# Pendeteksi_Kebusukan_Berbasis_IOT.net
KiCad netlist of a schematic drawn in EAGLE
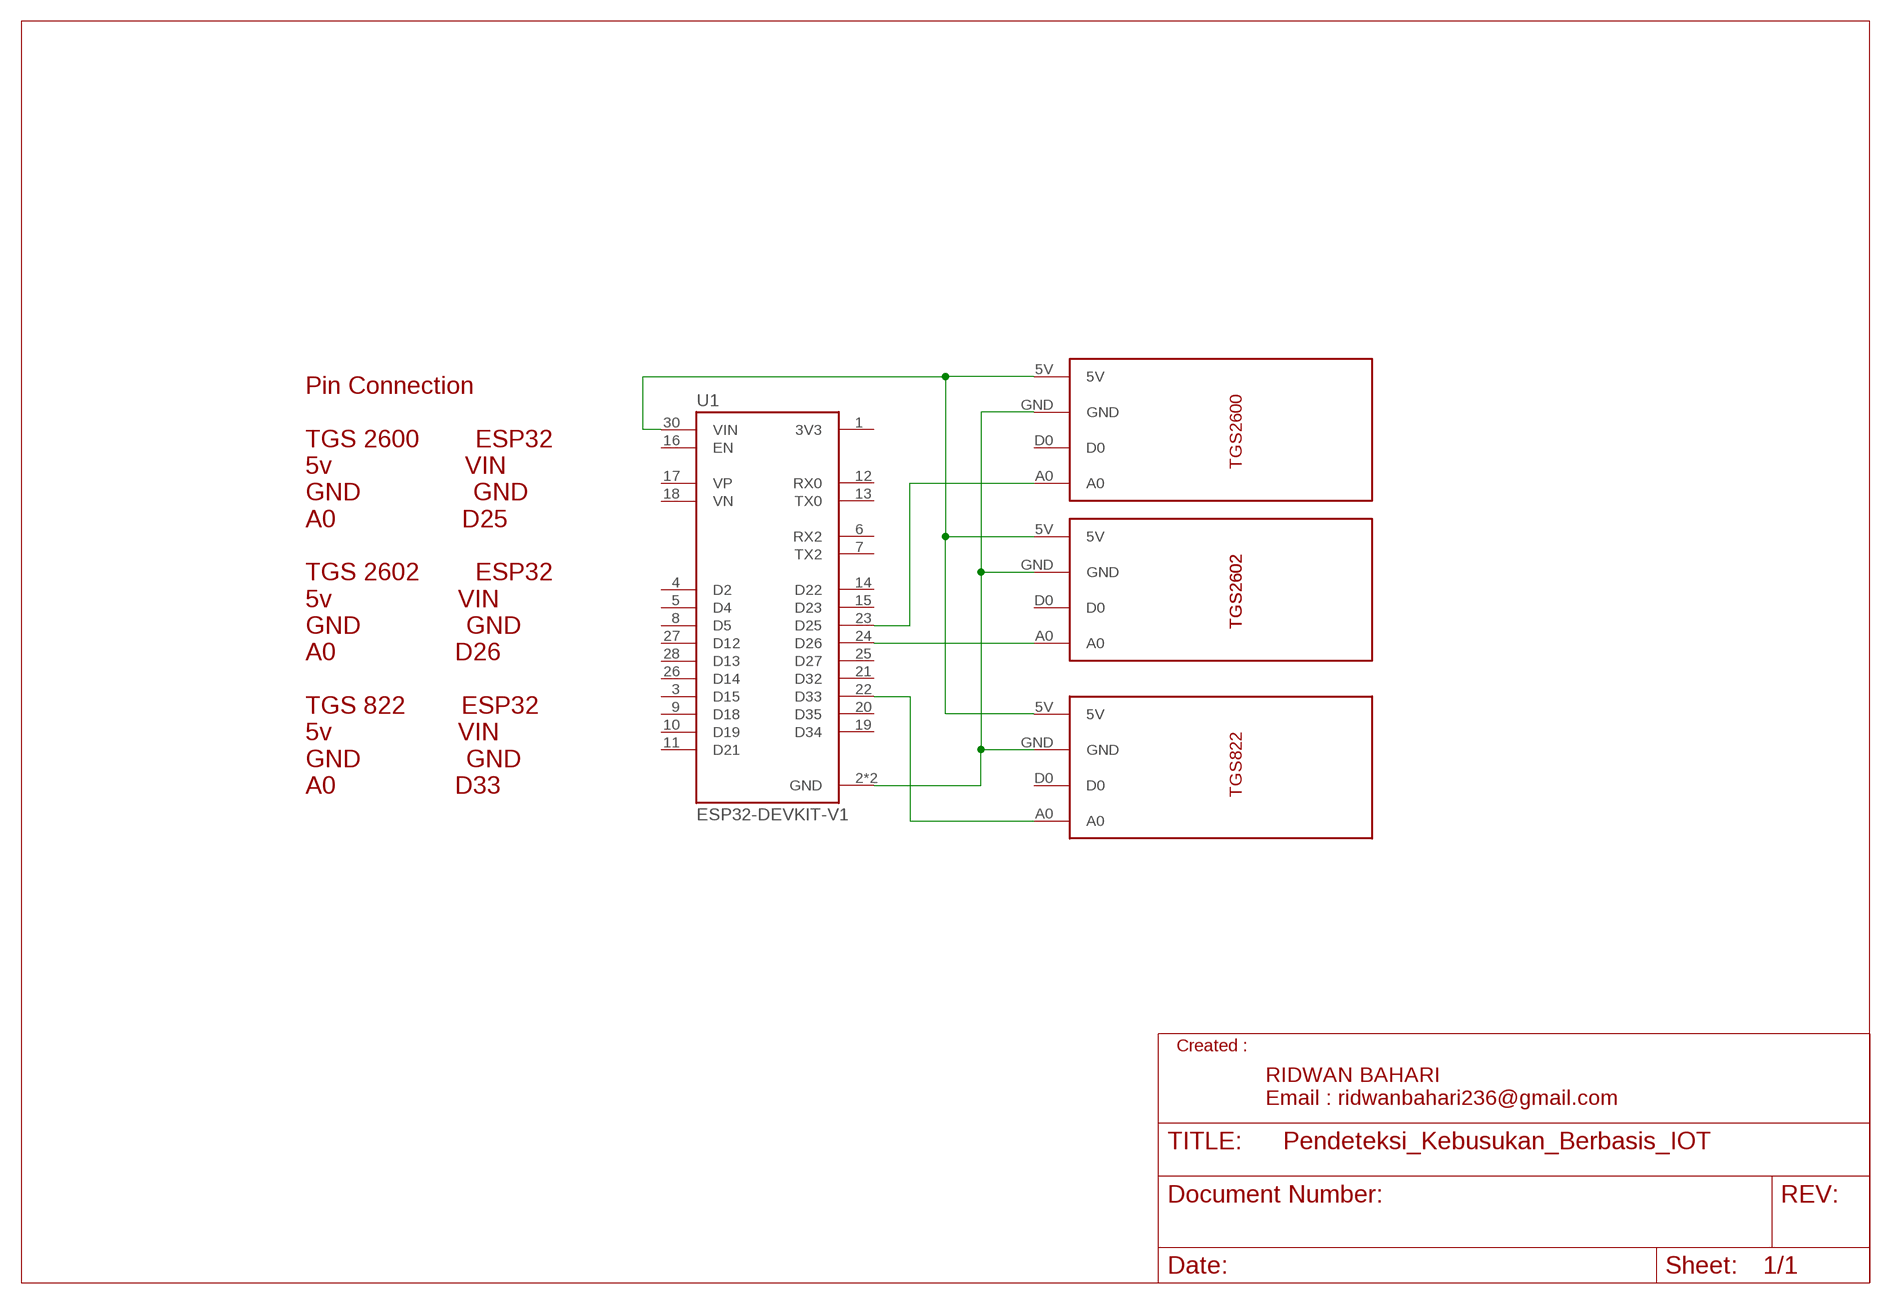
[diagram p0: schematic, sheet 1]

(export (version "E")
  (design (tool "Eeschema 10.0.6"))
  (components
    (comp (ref "SENSOR_GAS1")
      (value "SENSOR_GAS")
      (footprint "eagle-import:SENSOR_GAS")
      (libsource (lib "eagle-import") (part "SENSOR_GAS"))
    )
    (comp (ref "SENSOR_GAS2")
      (value "SENSOR_GAS")
      (footprint "eagle-import:SENSOR_GAS")
      (libsource (lib "eagle-import") (part "SENSOR_GAS"))
    )
    (comp (ref "SENSOR_GAS3")
      (value "SENSOR_GAS")
      (footprint "eagle-import:SENSOR_GAS")
      (libsource (lib "eagle-import") (part "SENSOR_GAS"))
    )
    (comp (ref "U1")
      (value "ESP32-DEVKIT-V1")
      (footprint "eagle-import:MODULE_ESP32_DEVKIT_V1")
      (fields (field (name "MF") "Do it"))
      (libsource (lib "eagle-import") (part "ESP32-DEVKIT-V1"))
    )
  )
  (nets
    (net (code "1") (name "Net-(SENSOR_GAS1-PadGND)") (class "Default")
      (node (ref "SENSOR_GAS1") (pin "GND") (pinfunction "GND_GND") (pintype "bidirectional"))
      (node (ref "SENSOR_GAS2") (pin "GND") (pinfunction "GND_GND") (pintype "bidirectional"))
      (node (ref "SENSOR_GAS3") (pin "GND") (pinfunction "GND_GND") (pintype "bidirectional"))
      (node (ref "U1") (pin "2") (pinfunction "GND_2") (pintype "power_in"))
      (node (ref "U1") (pin "29") (pinfunction "GND_29") (pintype "power_in"))
    )
    (net (code "2") (name "Net-(U1-D25)") (class "Default")
      (node (ref "SENSOR_GAS1") (pin "A0") (pinfunction "A0_A0") (pintype "bidirectional"))
      (node (ref "U1") (pin "23") (pinfunction "D25_23") (pintype "bidirectional"))
    )
    (net (code "3") (name "Net-(U1-D26)") (class "Default")
      (node (ref "SENSOR_GAS2") (pin "A0") (pinfunction "A0_A0") (pintype "bidirectional"))
      (node (ref "U1") (pin "24") (pinfunction "D26_24") (pintype "bidirectional"))
    )
    (net (code "4") (name "Net-(U1-D33)") (class "Default")
      (node (ref "SENSOR_GAS3") (pin "A0") (pinfunction "A0_A0") (pintype "bidirectional"))
      (node (ref "U1") (pin "22") (pinfunction "D33_22") (pintype "bidirectional"))
    )
    (net (code "5") (name "Net-(U1-VIN)") (class "Default")
      (node (ref "SENSOR_GAS1") (pin "5V") (pinfunction "5V_5V") (pintype "bidirectional"))
      (node (ref "SENSOR_GAS2") (pin "5V") (pinfunction "5V_5V") (pintype "bidirectional"))
      (node (ref "SENSOR_GAS3") (pin "5V") (pinfunction "5V_5V") (pintype "bidirectional"))
      (node (ref "U1") (pin "30") (pinfunction "VIN_30") (pintype "input"))
    )
    (net (code "6") (name "unconnected-(SENSOR_GAS1-PadD0)") (class "Default")
      (node (ref "SENSOR_GAS1") (pin "D0") (pinfunction "D0_D0") (pintype "bidirectional"))
    )
    (net (code "7") (name "unconnected-(SENSOR_GAS2-PadD0)") (class "Default")
      (node (ref "SENSOR_GAS2") (pin "D0") (pinfunction "D0_D0") (pintype "bidirectional"))
    )
    (net (code "8") (name "unconnected-(SENSOR_GAS3-PadD0)") (class "Default")
      (node (ref "SENSOR_GAS3") (pin "D0") (pinfunction "D0_D0") (pintype "bidirectional"))
    )
    (net (code "9") (name "unconnected-(U1-3V3-Pad1)") (class "Default")
      (node (ref "U1") (pin "1") (pinfunction "3V3_1") (pintype "output"))
    )
    (net (code "10") (name "unconnected-(U1-D2-Pad4)") (class "Default")
      (node (ref "U1") (pin "4") (pinfunction "D2_4") (pintype "bidirectional"))
    )
    (net (code "11") (name "unconnected-(U1-D4-Pad5)") (class "Default")
      (node (ref "U1") (pin "5") (pinfunction "D4_5") (pintype "bidirectional"))
    )
    (net (code "12") (name "unconnected-(U1-D5-Pad8)") (class "Default")
      (node (ref "U1") (pin "8") (pinfunction "D5_8") (pintype "bidirectional"))
    )
    (net (code "13") (name "unconnected-(U1-D12-Pad27)") (class "Default")
      (node (ref "U1") (pin "27") (pinfunction "D12_27") (pintype "bidirectional"))
    )
    (net (code "14") (name "unconnected-(U1-D13-Pad28)") (class "Default")
      (node (ref "U1") (pin "28") (pinfunction "D13_28") (pintype "bidirectional"))
    )
    (net (code "15") (name "unconnected-(U1-D14-Pad26)") (class "Default")
      (node (ref "U1") (pin "26") (pinfunction "D14_26") (pintype "bidirectional"))
    )
    (net (code "16") (name "unconnected-(U1-D15-Pad3)") (class "Default")
      (node (ref "U1") (pin "3") (pinfunction "D15_3") (pintype "bidirectional"))
    )
    (net (code "17") (name "unconnected-(U1-D18-Pad9)") (class "Default")
      (node (ref "U1") (pin "9") (pinfunction "D18_9") (pintype "bidirectional"))
    )
    (net (code "18") (name "unconnected-(U1-D19-Pad10)") (class "Default")
      (node (ref "U1") (pin "10") (pinfunction "D19_10") (pintype "bidirectional"))
    )
    (net (code "19") (name "unconnected-(U1-D21-Pad11)") (class "Default")
      (node (ref "U1") (pin "11") (pinfunction "D21_11") (pintype "bidirectional"))
    )
    (net (code "20") (name "unconnected-(U1-D22-Pad14)") (class "Default")
      (node (ref "U1") (pin "14") (pinfunction "D22_14") (pintype "bidirectional"))
    )
    (net (code "21") (name "unconnected-(U1-D23-Pad15)") (class "Default")
      (node (ref "U1") (pin "15") (pinfunction "D23_15") (pintype "bidirectional"))
    )
    (net (code "22") (name "unconnected-(U1-D27-Pad25)") (class "Default")
      (node (ref "U1") (pin "25") (pinfunction "D27_25") (pintype "bidirectional"))
    )
    (net (code "23") (name "unconnected-(U1-D32-Pad21)") (class "Default")
      (node (ref "U1") (pin "21") (pinfunction "D32_21") (pintype "bidirectional"))
    )
    (net (code "24") (name "unconnected-(U1-D34-Pad19)") (class "Default")
      (node (ref "U1") (pin "19") (pinfunction "D34_19") (pintype "bidirectional"))
    )
    (net (code "25") (name "unconnected-(U1-D35-Pad20)") (class "Default")
      (node (ref "U1") (pin "20") (pinfunction "D35_20") (pintype "bidirectional"))
    )
    (net (code "26") (name "unconnected-(U1-EN-Pad16)") (class "Default")
      (node (ref "U1") (pin "16") (pinfunction "EN_16") (pintype "input"))
    )
    (net (code "27") (name "unconnected-(U1-RX0-Pad12)") (class "Default")
      (node (ref "U1") (pin "12") (pinfunction "RX0_12") (pintype "input"))
    )
    (net (code "28") (name "unconnected-(U1-RX2-Pad6)") (class "Default")
      (node (ref "U1") (pin "6") (pinfunction "RX2_6") (pintype "input"))
    )
    (net (code "29") (name "unconnected-(U1-TX0-Pad13)") (class "Default")
      (node (ref "U1") (pin "13") (pinfunction "TX0_13") (pintype "output"))
    )
    (net (code "30") (name "unconnected-(U1-TX2-Pad7)") (class "Default")
      (node (ref "U1") (pin "7") (pinfunction "TX2_7") (pintype "output"))
    )
    (net (code "31") (name "unconnected-(U1-VN-Pad18)") (class "Default")
      (node (ref "U1") (pin "18") (pinfunction "VN_18") (pintype "bidirectional"))
    )
    (net (code "32") (name "unconnected-(U1-VP-Pad17)") (class "Default")
      (node (ref "U1") (pin "17") (pinfunction "VP_17") (pintype "bidirectional"))
    )
  )
)
